# Precharge.net
KiCad netlist of a schematic drawn in Altium Designer
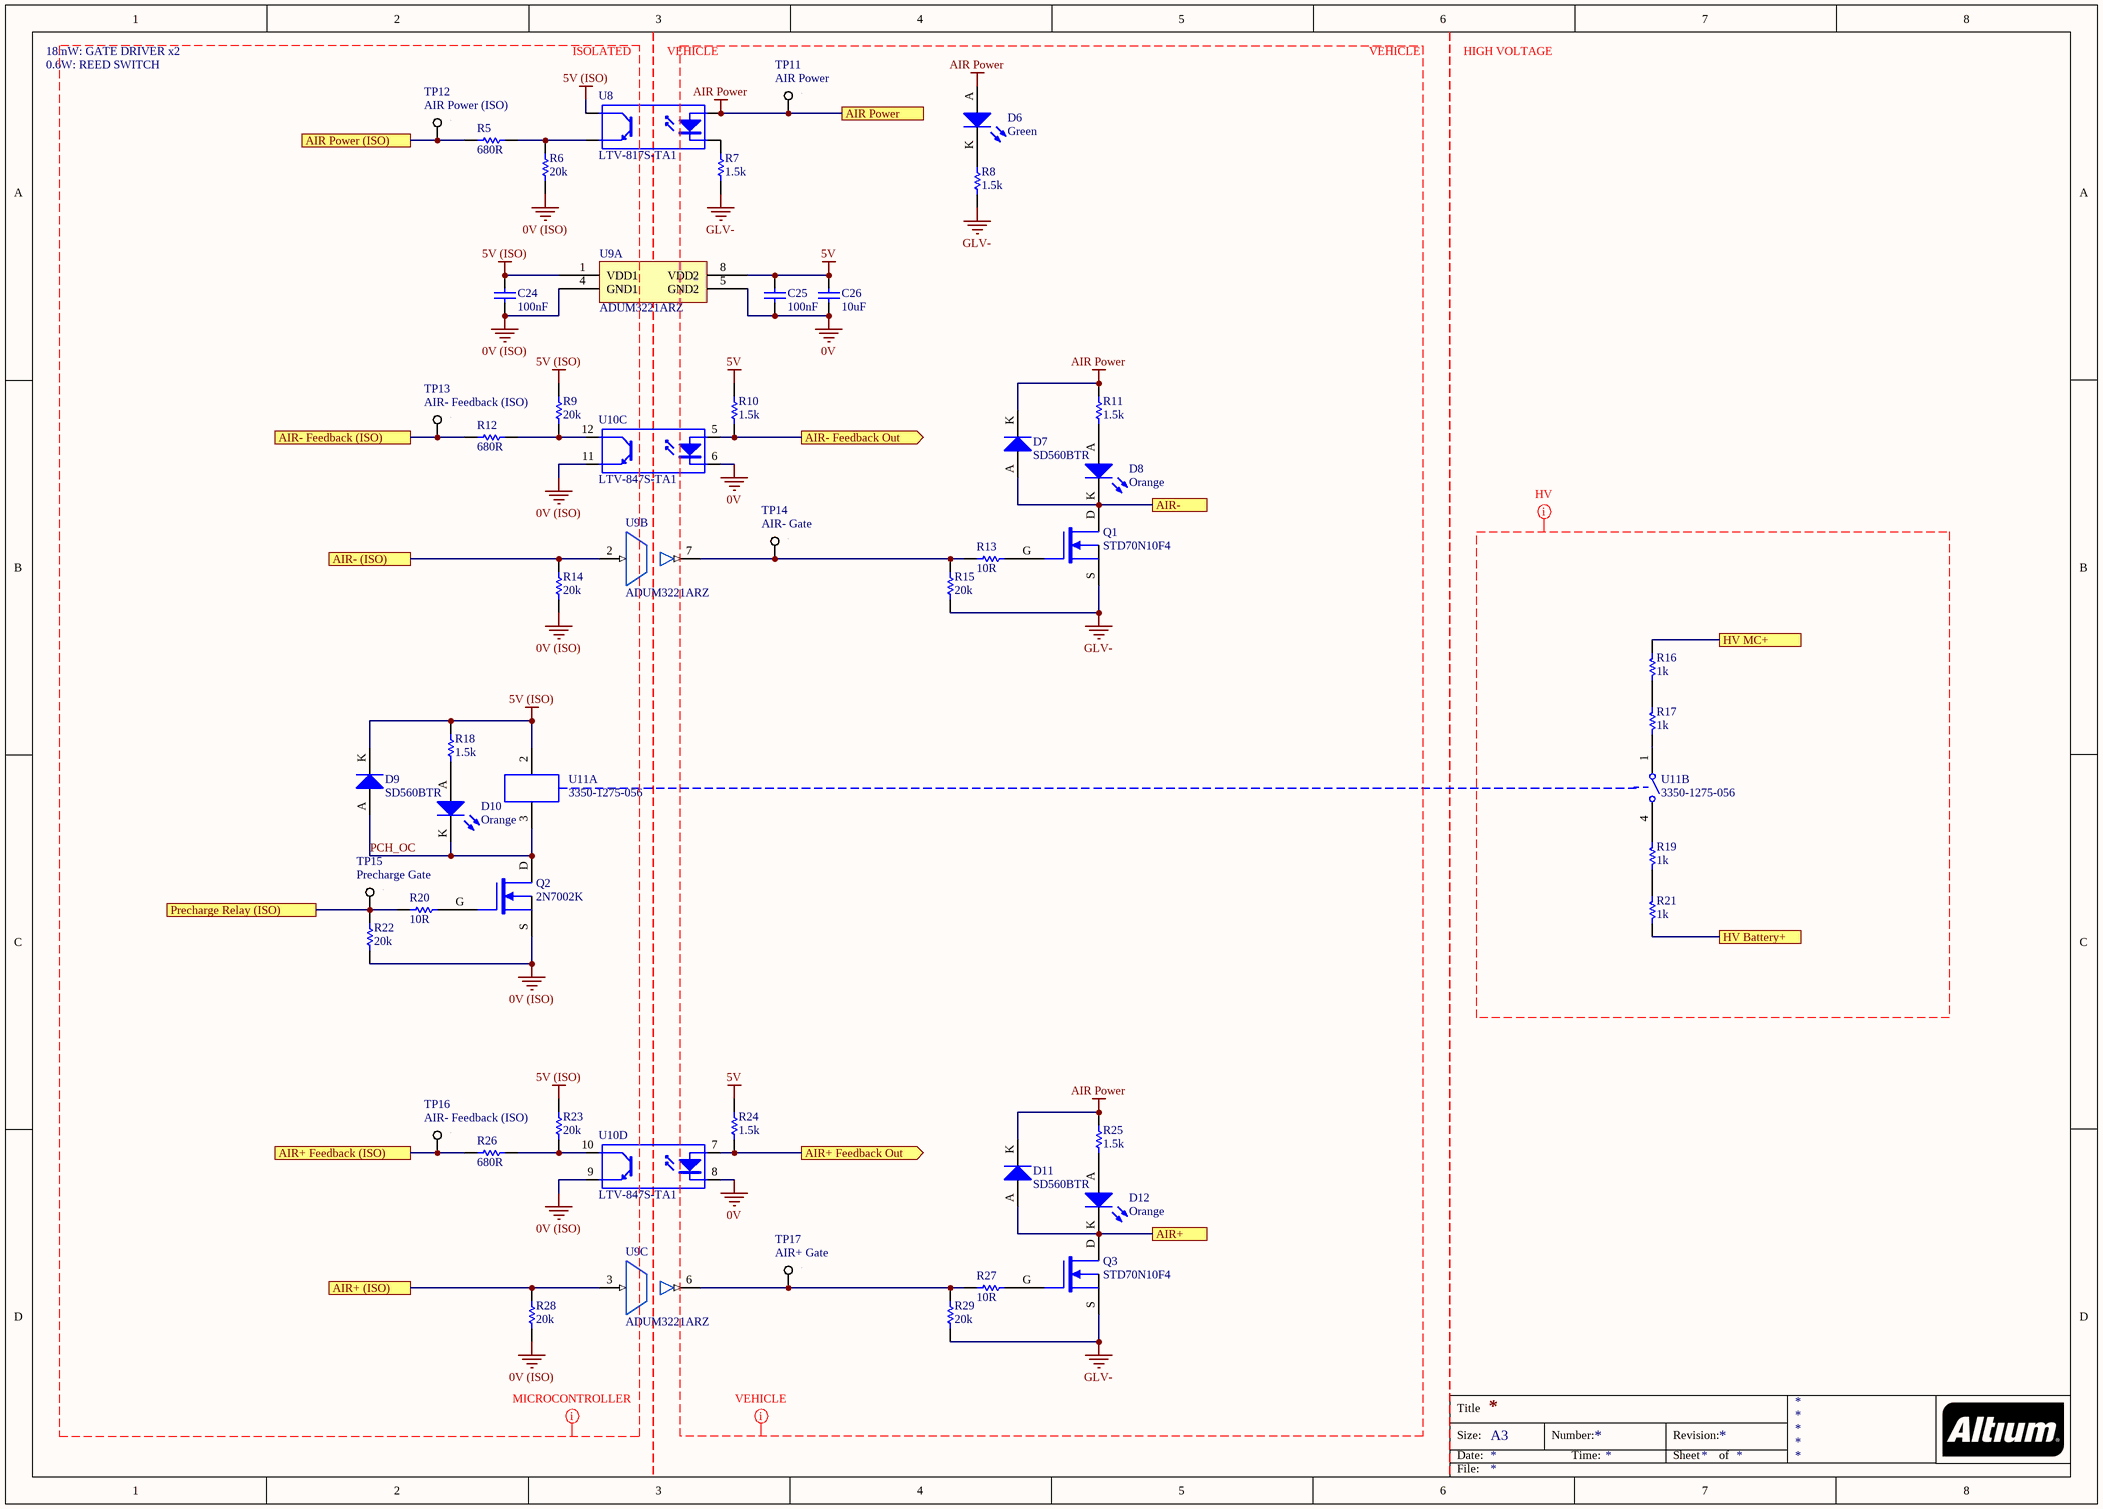
[diagram p0: Precharge.SchDoc]

(export (version "E")
  (design (tool "Eeschema 10.0.6"))
  (components
    (comp (ref "C24")
      (value "100nF")
      (footprint "0805")
      (fields
        (field (name "PART NUMBER") "GCM21BR71H104KA37L")
        (field (name "TOLERANCE") "±10%")
        (field (name "MANUFACTURER") "muRata")
      )
      (libsource (lib "ts_20-standard-library") (part "Capacitor"))
    )
    (comp (ref "C25")
      (value "100nF")
      (footprint "0805")
      (fields
        (field (name "PART NUMBER") "GCM21BR71H104KA37L")
        (field (name "TOLERANCE") "±10%")
        (field (name "MANUFACTURER") "muRata")
      )
      (libsource (lib "ts_20-standard-library") (part "Capacitor"))
    )
    (comp (ref "C26")
      (value "10uF")
      (footprint "0805")
      (fields
        (field (name "PART NUMBER") "GRM21BR6YA106KE43L")
        (field (name "TOLERANCE") "10%")
        (field (name "MANUFACTURER") "muRata")
      )
      (libsource (lib "ts_20-standard-library") (part "Capacitor"))
    )
    (comp (ref "D6")
      (value "Green")
      (footprint "0805 LED")
      (description "Green LED Indication - Discrete 1.75V 0805 (2012 Metric)")
      (fields (field (name "PART NUMBER") "SML-210FTT86") (field (name "MANUFACTURER") "ROHM Semiconductor"))
      (libsource (lib "ts_20-standard-library") (part "LED"))
    )
    (comp (ref "D7")
      (value "SD560BTR")
      (footprint "SMB Diode")
      (description "1.2V_F 600V 5A SMB")
      (fields
        (field (name "MANUFACTURER") "SMC Diode Solutions")
        (field (name "DIGIKEY PART NUMBER") "1655-1530-2-ND")
      )
      (libsource (lib "ts_20-standard-library") (part "Diode"))
    )
    (comp (ref "D8")
      (value "Orange")
      (footprint "0805 LED")
      (description "Orange LED Indication - Discrete 1.75V 0805 (2012 Metric)")
      (fields (field (name "PART NUMBER") "SML-211DTT86") (field (name "MANUFACTURER") "ROHM Semiconductor"))
      (libsource (lib "ts_20-standard-library") (part "LED"))
    )
    (comp (ref "D9")
      (value "SD560BTR")
      (footprint "SMB Diode")
      (description "1.2V_F 600V 5A SMB")
      (fields
        (field (name "MANUFACTURER") "SMC Diode Solutions")
        (field (name "DIGIKEY PART NUMBER") "1655-1530-2-ND")
      )
      (libsource (lib "ts_20-standard-library") (part "Diode"))
    )
    (comp (ref "D10")
      (value "Orange")
      (footprint "0805 LED")
      (description "Orange LED Indication - Discrete 1.75V 0805 (2012 Metric)")
      (fields (field (name "PART NUMBER") "SML-211DTT86") (field (name "MANUFACTURER") "ROHM Semiconductor"))
      (libsource (lib "ts_20-standard-library") (part "LED"))
    )
    (comp (ref "D11")
      (value "SD560BTR")
      (footprint "SMB Diode")
      (description "1.2V_F 600V 5A SMB")
      (fields
        (field (name "MANUFACTURER") "SMC Diode Solutions")
        (field (name "DIGIKEY PART NUMBER") "1655-1530-2-ND")
      )
      (libsource (lib "ts_20-standard-library") (part "Diode"))
    )
    (comp (ref "D12")
      (value "Orange")
      (footprint "0805 LED")
      (description "Orange LED Indication - Discrete 1.75V 0805 (2012 Metric)")
      (fields (field (name "PART NUMBER") "SML-211DTT86") (field (name "MANUFACTURER") "ROHM Semiconductor"))
      (libsource (lib "ts_20-standard-library") (part "LED"))
    )
    (comp (ref "Q1")
      (value "STD70N10F4")
      (footprint "STM TO-252 MOSFET")
      (description "N-Channel 100V 60A (Tc) 125W (Tc) Surface Mount DPAK")
      (fields
        (field (name "MANUFACTURER") "STMicroelectronics")
        (field (name "DIGIKEY PART NUMBER") "497-8806-2-ND")
        (field (name "PUBLISHER") "Altium Limited")
      )
      (libsource (lib "ts_20-standard-library") (part "MOSFET-N"))
    )
    (comp (ref "Q2")
      (value "2N7002K")
      (footprint "ON SOT-23 MOSFET")
      (description "60V 380mA, NFET MOSTFET (Small Signal)")
      (fields
        (field (name "MANUFACTURER") "ON Semiconductor")
        (field (name "DIGIKEY PART NUMBER") "2N7002KCT-ND")
        (field (name "PUBLISHER") "Altium Limited")
      )
      (libsource (lib "ts_20-standard-library") (part "MOSFET-N"))
    )
    (comp (ref "Q3")
      (value "STD70N10F4")
      (footprint "STM TO-252 MOSFET")
      (description "N-Channel 100V 60A (Tc) 125W (Tc) Surface Mount DPAK")
      (fields
        (field (name "MANUFACTURER") "STMicroelectronics")
        (field (name "DIGIKEY PART NUMBER") "497-8806-2-ND")
        (field (name "PUBLISHER") "Altium Limited")
      )
      (libsource (lib "ts_20-standard-library") (part "MOSFET-N"))
    )
    (comp (ref "R5")
      (value "680R")
      (footprint "0805")
      (fields
        (field (name "PART NUMBER") "RC0805FR07680RL")
        (field (name "MANUFACTURER") "YAGEO")
        (field (name "TOLERANCE") "0.01")
      )
      (libsource (lib "ts_20-standard-library") (part "Resistor"))
    )
    (comp (ref "R6")
      (value "20k")
      (footprint "0805")
      (fields
        (field (name "PART NUMBER") "RC0805FR0720KL")
        (field (name "MANUFACTURER") "YAGEO")
        (field (name "TOLERANCE") "0.01")
      )
      (libsource (lib "ts_20-standard-library") (part "Resistor"))
    )
    (comp (ref "R7")
      (value "1.5k")
      (footprint "0805")
      (fields
        (field (name "PART NUMBER") "RC0805FR071K5L")
        (field (name "MANUFACTURER") "YAGEO")
        (field (name "TOLERANCE") "0.01")
      )
      (libsource (lib "ts_20-standard-library") (part "Resistor"))
    )
    (comp (ref "R8")
      (value "1.5k")
      (footprint "0805")
      (fields
        (field (name "PART NUMBER") "RC0805FR071K5L")
        (field (name "MANUFACTURER") "YAGEO")
        (field (name "TOLERANCE") "0.01")
      )
      (libsource (lib "ts_20-standard-library") (part "Resistor"))
    )
    (comp (ref "R9")
      (value "20k")
      (footprint "0805")
      (fields
        (field (name "PART NUMBER") "RC0805FR0720KL")
        (field (name "MANUFACTURER") "YAGEO")
        (field (name "TOLERANCE") "0.01")
      )
      (libsource (lib "ts_20-standard-library") (part "Resistor"))
    )
    (comp (ref "R10")
      (value "1.5k")
      (footprint "0805")
      (fields
        (field (name "PART NUMBER") "RC0805FR071K5L")
        (field (name "MANUFACTURER") "YAGEO")
        (field (name "TOLERANCE") "0.01")
      )
      (libsource (lib "ts_20-standard-library") (part "Resistor"))
    )
    (comp (ref "R11")
      (value "1.5k")
      (footprint "0805")
      (fields
        (field (name "PART NUMBER") "RC0805FR071K5L")
        (field (name "MANUFACTURER") "YAGEO")
        (field (name "TOLERANCE") "0.01")
      )
      (libsource (lib "ts_20-standard-library") (part "Resistor"))
    )
    (comp (ref "R12")
      (value "680R")
      (footprint "0805")
      (fields
        (field (name "PART NUMBER") "RC0805FR07680RL")
        (field (name "MANUFACTURER") "YAGEO")
        (field (name "TOLERANCE") "0.01")
      )
      (libsource (lib "ts_20-standard-library") (part "Resistor"))
    )
    (comp (ref "R13")
      (value "10R")
      (footprint "0805")
      (fields
        (field (name "PART NUMBER") "RC0805FR0710RL")
        (field (name "MANUFACTURER") "YAGEO")
        (field (name "TOLERANCE") "0.01")
      )
      (libsource (lib "ts_20-standard-library") (part "Resistor"))
    )
    (comp (ref "R14")
      (value "20k")
      (footprint "0805")
      (fields
        (field (name "PART NUMBER") "RC0805FR0720KL")
        (field (name "MANUFACTURER") "YAGEO")
        (field (name "TOLERANCE") "0.01")
      )
      (libsource (lib "ts_20-standard-library") (part "Resistor"))
    )
    (comp (ref "R15")
      (value "20k")
      (footprint "0805")
      (fields
        (field (name "PART NUMBER") "RC0805FR0720KL")
        (field (name "MANUFACTURER") "YAGEO")
        (field (name "TOLERANCE") "0.01")
      )
      (libsource (lib "ts_20-standard-library") (part "Resistor"))
    )
    (comp (ref "R16")
      (value "1k")
      (footprint "B TO-263")
      (fields
        (field (name "PART NUMBER") "PWR263S-35-1001J")
        (field (name "MANUFACTURER") "Bournes Inc")
        (field (name "TOLERANCE") "0.05")
      )
      (libsource (lib "ts_20-standard-library") (part "Resistor"))
    )
    (comp (ref "R17")
      (value "1k")
      (footprint "B TO-263")
      (fields
        (field (name "PART NUMBER") "PWR263S-35-1001J")
        (field (name "MANUFACTURER") "Bournes Inc")
        (field (name "TOLERANCE") "0.05")
      )
      (libsource (lib "ts_20-standard-library") (part "Resistor"))
    )
    (comp (ref "R18")
      (value "1.5k")
      (footprint "0805")
      (fields
        (field (name "PART NUMBER") "RC0805FR071K5L")
        (field (name "MANUFACTURER") "YAGEO")
        (field (name "TOLERANCE") "0.01")
      )
      (libsource (lib "ts_20-standard-library") (part "Resistor"))
    )
    (comp (ref "R19")
      (value "1k")
      (footprint "B TO-263")
      (fields
        (field (name "PART NUMBER") "PWR263S-35-1001J")
        (field (name "MANUFACTURER") "Bournes Inc")
        (field (name "TOLERANCE") "0.05")
      )
      (libsource (lib "ts_20-standard-library") (part "Resistor"))
    )
    (comp (ref "R20")
      (value "10R")
      (footprint "0805")
      (fields
        (field (name "PART NUMBER") "RC0805FR0710RL")
        (field (name "MANUFACTURER") "YAGEO")
        (field (name "TOLERANCE") "0.01")
      )
      (libsource (lib "ts_20-standard-library") (part "Resistor"))
    )
    (comp (ref "R21")
      (value "1k")
      (footprint "B TO-263")
      (fields
        (field (name "PART NUMBER") "PWR263S-35-1001J")
        (field (name "MANUFACTURER") "Bournes Inc")
        (field (name "TOLERANCE") "0.05")
      )
      (libsource (lib "ts_20-standard-library") (part "Resistor"))
    )
    (comp (ref "R22")
      (value "20k")
      (footprint "0805")
      (fields
        (field (name "PART NUMBER") "RC0805FR0720KL")
        (field (name "MANUFACTURER") "YAGEO")
        (field (name "TOLERANCE") "0.01")
      )
      (libsource (lib "ts_20-standard-library") (part "Resistor"))
    )
    (comp (ref "R23")
      (value "20k")
      (footprint "0805")
      (fields
        (field (name "PART NUMBER") "RC0805FR0720KL")
        (field (name "MANUFACTURER") "YAGEO")
        (field (name "TOLERANCE") "0.01")
      )
      (libsource (lib "ts_20-standard-library") (part "Resistor"))
    )
    (comp (ref "R24")
      (value "1.5k")
      (footprint "0805")
      (fields
        (field (name "PART NUMBER") "RC0805FR071K5L")
        (field (name "MANUFACTURER") "YAGEO")
        (field (name "TOLERANCE") "0.01")
      )
      (libsource (lib "ts_20-standard-library") (part "Resistor"))
    )
    (comp (ref "R25")
      (value "1.5k")
      (footprint "0805")
      (fields
        (field (name "PART NUMBER") "RC0805FR071K5L")
        (field (name "MANUFACTURER") "YAGEO")
        (field (name "TOLERANCE") "0.01")
      )
      (libsource (lib "ts_20-standard-library") (part "Resistor"))
    )
    (comp (ref "R26")
      (value "680R")
      (footprint "0805")
      (fields
        (field (name "PART NUMBER") "RC0805FR07680RL")
        (field (name "MANUFACTURER") "YAGEO")
        (field (name "TOLERANCE") "0.01")
      )
      (libsource (lib "ts_20-standard-library") (part "Resistor"))
    )
    (comp (ref "R27")
      (value "10R")
      (footprint "0805")
      (fields
        (field (name "PART NUMBER") "RC0805FR0710RL")
        (field (name "MANUFACTURER") "YAGEO")
        (field (name "TOLERANCE") "0.01")
      )
      (libsource (lib "ts_20-standard-library") (part "Resistor"))
    )
    (comp (ref "R28")
      (value "20k")
      (footprint "0805")
      (fields
        (field (name "PART NUMBER") "RC0805FR0720KL")
        (field (name "MANUFACTURER") "YAGEO")
        (field (name "TOLERANCE") "0.01")
      )
      (libsource (lib "ts_20-standard-library") (part "Resistor"))
    )
    (comp (ref "R29")
      (value "20k")
      (footprint "0805")
      (fields
        (field (name "PART NUMBER") "RC0805FR0720KL")
        (field (name "MANUFACTURER") "YAGEO")
        (field (name "TOLERANCE") "0.01")
      )
      (libsource (lib "ts_20-standard-library") (part "Resistor"))
    )
    (comp (ref "TP11")
      (value "AIR Power")
      (footprint "SMD Test Point 1mm")
      (fields (field (name "PART NUMBER") "SMD Test Point Small") (field (name "CONTACT") "NA"))
      (libsource (lib "ts_20-standard-connectors") (part "Test Point Small"))
    )
    (comp (ref "TP12")
      (value "AIR Power (ISO)")
      (footprint "SMD Test Point 1mm")
      (fields (field (name "PART NUMBER") "SMD Test Point Small") (field (name "CONTACT") "NA"))
      (libsource (lib "ts_20-standard-connectors") (part "Test Point Small"))
    )
    (comp (ref "TP13")
      (value "AIR- Feedback (ISO)")
      (footprint "SMD Test Point 1mm")
      (fields (field (name "PART NUMBER") "SMD Test Point Small") (field (name "CONTACT") "NA"))
      (libsource (lib "ts_20-standard-connectors") (part "Test Point Small"))
    )
    (comp (ref "TP14")
      (value "AIR- Gate")
      (footprint "SMD Test Point 1mm")
      (fields (field (name "PART NUMBER") "SMD Test Point Small") (field (name "CONTACT") "NA"))
      (libsource (lib "ts_20-standard-connectors") (part "Test Point Small"))
    )
    (comp (ref "TP15")
      (value "Precharge Gate")
      (footprint "SMD Test Point 1mm")
      (fields (field (name "PART NUMBER") "SMD Test Point Small") (field (name "CONTACT") "NA"))
      (libsource (lib "ts_20-standard-connectors") (part "Test Point Small"))
    )
    (comp (ref "TP16")
      (value "AIR- Feedback (ISO)")
      (footprint "SMD Test Point 1mm")
      (fields (field (name "PART NUMBER") "SMD Test Point Small") (field (name "CONTACT") "NA"))
      (libsource (lib "ts_20-standard-connectors") (part "Test Point Small"))
    )
    (comp (ref "TP17")
      (value "AIR+ Gate")
      (footprint "SMD Test Point 1mm")
      (fields (field (name "PART NUMBER") "SMD Test Point Small") (field (name "CONTACT") "NA"))
      (libsource (lib "ts_20-standard-connectors") (part "Test Point Small"))
    )
    (comp (ref "U8")
      (value "LTV-817S-TA1")
      (footprint "ON 4-SMD")
      (description "35V 50ma Optocoupler (VF=1.2V)")
      (fields
        (field (name "MANUFACTURER") "Lite-On Inc")
        (field (name "DIGIKEY PART NUMBER") "160-1893-2-ND")
      )
      (libsource (lib "ts_20-standard-library") (part "LTV-817S-TA1"))
    )
    (comp (ref "U9")
      (value "ADUM3221ARZ")
      (footprint "AD 8-SOIC")
      (description "4A Gate Driver Magnetic Coupling 2500Vrms 2 Channel 8-SOIC")
      (fields
        (field (name "MANUFACTURER") "Analog Devices")
        (field (name "DIGIKEY PART NUMBER") "ADUM3221ARZ-ND")
      )
      (libsource (lib "ts_20-standard-library") (part "ADuM3221"))
    )
    (comp (ref "U10")
      (value "LTV-847S-TA1")
      (footprint "ON 16-SMD")
      (description "Optoisolator Transistor Output 5000Vrms 4 Channel 16-SMD")
      (fields
        (field (name "MANUFACTURER") "Lite-On Inc")
        (field (name "DIGIKEY PART NUMBER") "160-1371-5-ND")
      )
      (libsource (lib "ts_20-standard-library") (part "LTV-847S-TA1"))
    )
    (comp (ref "U11")
      (value "3350-1275-056")
      (footprint "CI SPST")
      (description "RELAY REED HV SPST 200W 3A 5V (NO)")
      (fields
        (field (name "MANUFACTURER") "Comus International")
        (field (name "DIGIKEY PART NUMBER") "1835-1036-ND")
      )
      (libsource (lib "") (part "3350-1275-056_1"))
    )
  )
  (nets
    (net (code "1") (name "/AIR Power (ISO)") (class "Default")
      (node (ref "R5") (pin "1") (pinfunction "1_1") (pintype "passive"))
      (node (ref "TP12") (pin "1") (pinfunction "1_1") (pintype "passive"))
    )
    (net (code "2") (name "/AIR+") (class "Default")
      (node (ref "D11") (pin "A") (pinfunction "A_A") (pintype "passive"))
      (node (ref "D12") (pin "K") (pinfunction "K_K") (pintype "passive"))
      (node (ref "Q3") (pin "D") (pinfunction "D_D") (pintype "passive"))
    )
    (net (code "3") (name "/AIR+ (ISO)") (class "Default")
      (node (ref "R28") (pin "2") (pinfunction "2_2") (pintype "passive"))
      (node (ref "U9") (pin "3") (pinfunction "VIA_3") (pintype "input"))
    )
    (net (code "4") (name "/AIR+ Feedback (ISO)") (class "Default")
      (node (ref "R26") (pin "1") (pinfunction "1_1") (pintype "passive"))
      (node (ref "TP16") (pin "1") (pinfunction "1_1") (pintype "passive"))
    )
    (net (code "5") (name "/AIR+ Feedback Out") (class "Default")
      (node (ref "R24") (pin "1") (pinfunction "1_1") (pintype "passive"))
      (node (ref "U10") (pin "7") (pinfunction "A_7") (pintype "passive"))
    )
    (net (code "6") (name "/AIR-") (class "Default")
      (node (ref "D7") (pin "A") (pinfunction "A_A") (pintype "passive"))
      (node (ref "D8") (pin "K") (pinfunction "K_K") (pintype "passive"))
      (node (ref "Q1") (pin "D") (pinfunction "D_D") (pintype "passive"))
    )
    (net (code "7") (name "/AIR- (ISO)") (class "Default")
      (node (ref "R14") (pin "2") (pinfunction "2_2") (pintype "passive"))
      (node (ref "U9") (pin "2") (pinfunction "VIA_2") (pintype "input"))
    )
    (net (code "8") (name "/AIR- Feedback (ISO)") (class "Default")
      (node (ref "R12") (pin "1") (pinfunction "1_1") (pintype "passive"))
      (node (ref "TP13") (pin "1") (pinfunction "1_1") (pintype "passive"))
    )
    (net (code "9") (name "/AIR- Feedback Out") (class "Default")
      (node (ref "R10") (pin "1") (pinfunction "1_1") (pintype "passive"))
      (node (ref "U10") (pin "5") (pinfunction "A_5") (pintype "passive"))
    )
    (net (code "10") (name "/HV Battery+") (class "Default")
      (node (ref "R21") (pin "1") (pinfunction "1_1") (pintype "passive"))
    )
    (net (code "11") (name "/HV MC+") (class "Default")
      (node (ref "R16") (pin "2") (pinfunction "2_2") (pintype "passive"))
    )
    (net (code "12") (name "/PCH_OC") (class "Default")
      (node (ref "D10") (pin "K") (pinfunction "K_K") (pintype "passive"))
      (node (ref "D9") (pin "A") (pinfunction "A_A") (pintype "passive"))
      (node (ref "Q2") (pin "D") (pinfunction "D_D") (pintype "passive"))
      (node (ref "U11") (pin "3") (pinfunction "3_3") (pintype "passive"))
    )
    (net (code "13") (name "/Precharge Relay (ISO)") (class "Default")
      (node (ref "R20") (pin "1") (pinfunction "1_1") (pintype "passive"))
      (node (ref "R22") (pin "2") (pinfunction "2_2") (pintype "passive"))
      (node (ref "TP15") (pin "1") (pinfunction "1_1") (pintype "passive"))
    )
    (net (code "14") (name "0V") (class "Default")
      (node (ref "C25") (pin "1") (pinfunction "1_1") (pintype "passive"))
      (node (ref "C26") (pin "1") (pinfunction "1_1") (pintype "passive"))
      (node (ref "U10") (pin "6") (pinfunction "K_6") (pintype "passive"))
      (node (ref "U10") (pin "8") (pinfunction "K_8") (pintype "passive"))
      (node (ref "U9") (pin "5") (pinfunction "GND2_5") (pintype "passive"))
    )
    (net (code "15") (name "0V (ISO)") (class "Default")
      (node (ref "C24") (pin "1") (pinfunction "1_1") (pintype "passive"))
      (node (ref "Q2") (pin "S") (pinfunction "S_S") (pintype "passive"))
      (node (ref "R14") (pin "1") (pinfunction "1_1") (pintype "passive"))
      (node (ref "R22") (pin "1") (pinfunction "1_1") (pintype "passive"))
      (node (ref "R28") (pin "1") (pinfunction "1_1") (pintype "passive"))
      (node (ref "R6") (pin "1") (pinfunction "1_1") (pintype "passive"))
      (node (ref "U10") (pin "11") (pinfunction "E_11") (pintype "passive"))
      (node (ref "U10") (pin "9") (pinfunction "E_9") (pintype "passive"))
      (node (ref "U9") (pin "4") (pinfunction "GND1_4") (pintype "passive"))
    )
    (net (code "16") (name "5V") (class "Default")
      (node (ref "C25") (pin "2") (pinfunction "2_2") (pintype "passive"))
      (node (ref "C26") (pin "2") (pinfunction "2_2") (pintype "passive"))
      (node (ref "R10") (pin "2") (pinfunction "2_2") (pintype "passive"))
      (node (ref "R24") (pin "2") (pinfunction "2_2") (pintype "passive"))
      (node (ref "U9") (pin "8") (pinfunction "VDD2_8") (pintype "passive"))
    )
    (net (code "17") (name "5V (ISO)") (class "Default")
      (node (ref "C24") (pin "2") (pinfunction "2_2") (pintype "passive"))
      (node (ref "D9") (pin "K") (pinfunction "K_K") (pintype "passive"))
      (node (ref "R18") (pin "2") (pinfunction "2_2") (pintype "passive"))
      (node (ref "R23") (pin "2") (pinfunction "2_2") (pintype "passive"))
      (node (ref "R9") (pin "2") (pinfunction "2_2") (pintype "passive"))
      (node (ref "U11") (pin "2") (pinfunction "2_2") (pintype "passive"))
      (node (ref "U8") (pin "4") (pinfunction "C_4") (pintype "passive"))
      (node (ref "U9") (pin "1") (pinfunction "VDD1_1") (pintype "passive"))
    )
    (net (code "18") (name "AIR Power") (class "Default")
      (node (ref "D11") (pin "K") (pinfunction "K_K") (pintype "passive"))
      (node (ref "D6") (pin "A") (pinfunction "A_A") (pintype "passive"))
      (node (ref "D7") (pin "K") (pinfunction "K_K") (pintype "passive"))
      (node (ref "R11") (pin "2") (pinfunction "2_2") (pintype "passive"))
      (node (ref "R25") (pin "2") (pinfunction "2_2") (pintype "passive"))
      (node (ref "TP11") (pin "1") (pinfunction "1_1") (pintype "passive"))
      (node (ref "U8") (pin "1") (pinfunction "A_1") (pintype "passive"))
    )
    (net (code "19") (name "GLV-") (class "Default")
      (node (ref "Q1") (pin "S") (pinfunction "S_S") (pintype "passive"))
      (node (ref "Q3") (pin "S") (pinfunction "S_S") (pintype "passive"))
      (node (ref "R15") (pin "1") (pinfunction "1_1") (pintype "passive"))
      (node (ref "R29") (pin "1") (pinfunction "1_1") (pintype "passive"))
      (node (ref "R7") (pin "2") (pinfunction "2_2") (pintype "passive"))
      (node (ref "R8") (pin "2") (pinfunction "2_2") (pintype "passive"))
    )
    (net (code "20") (name "Net-(D6-PadK)") (class "Default")
      (node (ref "D6") (pin "K") (pinfunction "K_K") (pintype "passive"))
      (node (ref "R8") (pin "1") (pinfunction "1_1") (pintype "passive"))
    )
    (net (code "21") (name "Net-(D8-PadA)") (class "Default")
      (node (ref "D8") (pin "A") (pinfunction "A_A") (pintype "passive"))
      (node (ref "R11") (pin "1") (pinfunction "1_1") (pintype "passive"))
    )
    (net (code "22") (name "Net-(D10-PadA)") (class "Default")
      (node (ref "D10") (pin "A") (pinfunction "A_A") (pintype "passive"))
      (node (ref "R18") (pin "1") (pinfunction "1_1") (pintype "passive"))
    )
    (net (code "23") (name "Net-(D12-PadA)") (class "Default")
      (node (ref "D12") (pin "A") (pinfunction "A_A") (pintype "passive"))
      (node (ref "R25") (pin "1") (pinfunction "1_1") (pintype "passive"))
    )
    (net (code "24") (name "Net-(Q1-PadG)") (class "Default")
      (node (ref "Q1") (pin "G") (pinfunction "G_G") (pintype "passive"))
      (node (ref "R13") (pin "2") (pinfunction "2_2") (pintype "passive"))
    )
    (net (code "25") (name "Net-(Q2-PadG)") (class "Default")
      (node (ref "Q2") (pin "G") (pinfunction "G_G") (pintype "passive"))
      (node (ref "R20") (pin "2") (pinfunction "2_2") (pintype "passive"))
    )
    (net (code "26") (name "Net-(Q3-PadG)") (class "Default")
      (node (ref "Q3") (pin "G") (pinfunction "G_G") (pintype "passive"))
      (node (ref "R27") (pin "2") (pinfunction "2_2") (pintype "passive"))
    )
    (net (code "27") (name "Net-(R16-Pad1)") (class "Default")
      (node (ref "R16") (pin "1") (pinfunction "1_1") (pintype "passive"))
      (node (ref "R17") (pin "2") (pinfunction "2_2") (pintype "passive"))
    )
    (net (code "28") (name "Net-(R17-Pad1)") (class "Default")
      (node (ref "R17") (pin "1") (pinfunction "1_1") (pintype "passive"))
      (node (ref "U11") (pin "1") (pinfunction "1_1") (pintype "passive"))
    )
    (net (code "29") (name "Net-(R19-Pad1)") (class "Default")
      (node (ref "R19") (pin "1") (pinfunction "1_1") (pintype "passive"))
      (node (ref "R21") (pin "2") (pinfunction "2_2") (pintype "passive"))
    )
    (net (code "30") (name "Net-(R19-Pad2)") (class "Default")
      (node (ref "R19") (pin "2") (pinfunction "2_2") (pintype "passive"))
      (node (ref "U11") (pin "4") (pinfunction "4_4") (pintype "passive"))
    )
    (net (code "31") (name "Net-(U8-E)") (class "Default")
      (node (ref "R5") (pin "2") (pinfunction "2_2") (pintype "passive"))
      (node (ref "R6") (pin "2") (pinfunction "2_2") (pintype "passive"))
      (node (ref "U8") (pin "3") (pinfunction "E_3") (pintype "passive"))
    )
    (net (code "32") (name "Net-(U8-K)") (class "Default")
      (node (ref "R7") (pin "1") (pinfunction "1_1") (pintype "passive"))
      (node (ref "U8") (pin "2") (pinfunction "K_2") (pintype "passive"))
    )
    (net (code "33") (name "Net-(U9B-VOA)") (class "Default")
      (node (ref "R13") (pin "1") (pinfunction "1_1") (pintype "passive"))
      (node (ref "R15") (pin "2") (pinfunction "2_2") (pintype "passive"))
      (node (ref "TP14") (pin "1") (pinfunction "1_1") (pintype "passive"))
      (node (ref "U9") (pin "7") (pinfunction "VOA_7") (pintype "output"))
    )
    (net (code "34") (name "Net-(U9C-VOA)") (class "Default")
      (node (ref "R27") (pin "1") (pinfunction "1_1") (pintype "passive"))
      (node (ref "R29") (pin "2") (pinfunction "2_2") (pintype "passive"))
      (node (ref "TP17") (pin "1") (pinfunction "1_1") (pintype "passive"))
      (node (ref "U9") (pin "6") (pinfunction "VOA_6") (pintype "output"))
    )
    (net (code "35") (name "Net-(U10C-C)") (class "Default")
      (node (ref "R12") (pin "2") (pinfunction "2_2") (pintype "passive"))
      (node (ref "R9") (pin "1") (pinfunction "1_1") (pintype "passive"))
      (node (ref "U10") (pin "12") (pinfunction "C_12") (pintype "passive"))
    )
    (net (code "36") (name "Net-(U10D-C)") (class "Default")
      (node (ref "R23") (pin "1") (pinfunction "1_1") (pintype "passive"))
      (node (ref "R26") (pin "2") (pinfunction "2_2") (pintype "passive"))
      (node (ref "U10") (pin "10") (pinfunction "C_10") (pintype "passive"))
    )
  )
)
